# agouti.net
KiCad netlist of a schematic drawn in EAGLE
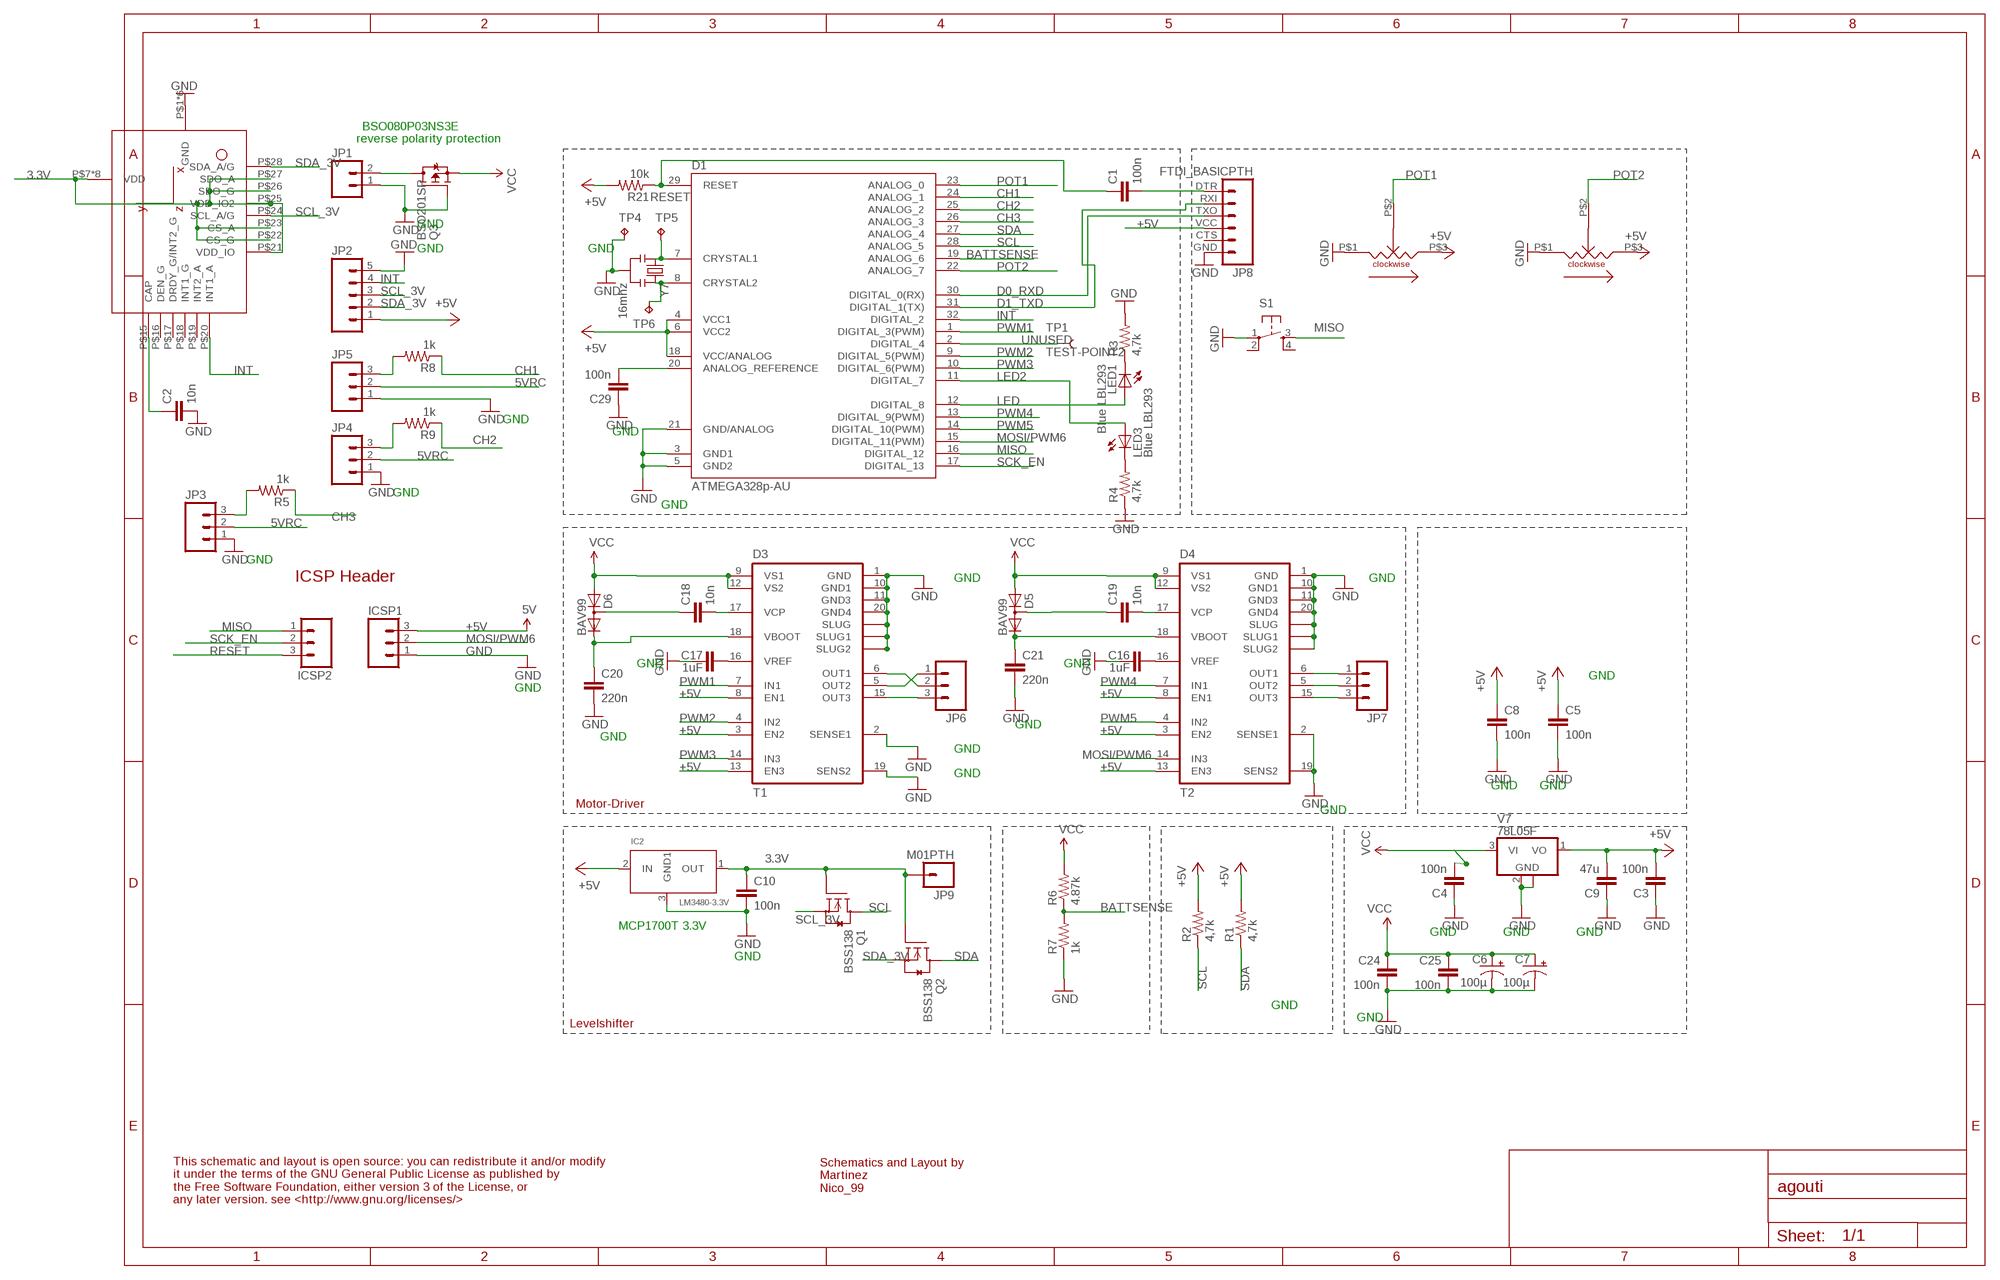
[diagram p0: schematic, sheet 1]

(export (version "E")
  (design (tool "Eeschema 10.0.6"))
  (components
    (comp (ref "C1")
      (value "100n")
      (footprint "eagle-import:0805")
      (libsource (lib "eagle-import") (part "CAP0805"))
    )
    (comp (ref "C2")
      (value "10n")
      (footprint "eagle-import:0805")
      (libsource (lib "eagle-import") (part "CAP0805"))
    )
    (comp (ref "C3")
      (value "100n")
      (footprint "eagle-import:0805")
      (libsource (lib "eagle-import") (part "CAP0805"))
    )
    (comp (ref "C4")
      (value "100n")
      (footprint "eagle-import:0805")
      (libsource (lib "eagle-import") (part "CAP0805"))
    )
    (comp (ref "C5")
      (value "100n")
      (footprint "eagle-import:0805")
      (libsource (lib "eagle-import") (part "CAP0805"))
    )
    (comp (ref "C6")
      (value "100µ")
      (footprint "eagle-import:PANASONIC_D")
      (libsource (lib "eagle-import") (part "CAP_POLD"))
    )
    (comp (ref "C7")
      (value "100µ")
      (footprint "eagle-import:PANASONIC_D")
      (libsource (lib "eagle-import") (part "CAP_POLD"))
    )
    (comp (ref "C8")
      (value "100n")
      (footprint "eagle-import:0805")
      (libsource (lib "eagle-import") (part "CAP0805"))
    )
    (comp (ref "C9")
      (value "47u")
      (footprint "eagle-import:C1210")
      (libsource (lib "eagle-import") (part "C-EUC1210"))
    )
    (comp (ref "C10")
      (value "100n")
      (footprint "eagle-import:0805")
      (libsource (lib "eagle-import") (part "CAP0805"))
    )
    (comp (ref "C16")
      (value "1uF")
      (footprint "eagle-import:0805")
      (libsource (lib "eagle-import") (part "CAP0805"))
    )
    (comp (ref "C17")
      (value "1uF")
      (footprint "eagle-import:0805")
      (libsource (lib "eagle-import") (part "CAP0805"))
    )
    (comp (ref "C18")
      (value "10n")
      (footprint "eagle-import:0805")
      (libsource (lib "eagle-import") (part "CAP0805"))
    )
    (comp (ref "C19")
      (value "10n")
      (footprint "eagle-import:0805")
      (libsource (lib "eagle-import") (part "CAP0805"))
    )
    (comp (ref "C20")
      (value "220n")
      (footprint "eagle-import:0805")
      (libsource (lib "eagle-import") (part "CAP0805"))
    )
    (comp (ref "C21")
      (value "220n")
      (footprint "eagle-import:0805")
      (libsource (lib "eagle-import") (part "CAP0805"))
    )
    (comp (ref "C24")
      (value "100n")
      (footprint "eagle-import:0805")
      (libsource (lib "eagle-import") (part "CAP0805"))
    )
    (comp (ref "C25")
      (value "100n")
      (footprint "eagle-import:0805")
      (libsource (lib "eagle-import") (part "CAP0805"))
    )
    (comp (ref "C29")
      (value "100n")
      (footprint "eagle-import:0805")
      (libsource (lib "eagle-import") (part "CAP0805"))
    )
    (comp (ref "D1")
      (value "ATMEGA328p-AU")
      (footprint "eagle-import:TQFP32-08")
      (libsource (lib "eagle-import") (part "ATMEGA168-AU"))
    )
    (comp (ref "D3")
      (value "T1")
      (footprint "eagle-import:SO20POWER2")
      (libsource (lib "eagle-import") (part "L6234"))
    )
    (comp (ref "D4")
      (value "T2")
      (footprint "eagle-import:SO20POWER2")
      (libsource (lib "eagle-import") (part "L6234"))
    )
    (comp (ref "D5")
      (value "BAV99")
      (footprint "eagle-import:SOT23")
      (libsource (lib "eagle-import") (part "BAV199"))
    )
    (comp (ref "D6")
      (value "BAV99")
      (footprint "eagle-import:SOT23")
      (libsource (lib "eagle-import") (part "BAV199"))
    )
    (comp (ref "IC2")
      (value "LM3480-3.3V")
      (footprint "eagle-import:SOT23")
      (libsource (lib "eagle-import") (part "VREG_MULTI2"))
    )
    (comp (ref "ICSP1")
      (value "M03PTH")
      (footprint "eagle-import:1X03")
      (libsource (lib "eagle-import") (part "SparkFun-Connectors_M03PTH"))
    )
    (comp (ref "ICSP2")
      (value "M03PTH")
      (footprint "eagle-import:1X03")
      (libsource (lib "eagle-import") (part "SparkFun-Connectors_M03PTH"))
    )
    (comp (ref "JP1")
      (value "M02PTH")
      (footprint "eagle-import:1X02")
      (libsource (lib "eagle-import") (part "M02PTH"))
    )
    (comp (ref "JP2")
      (value "M05PTH")
      (footprint "eagle-import:1X05")
      (libsource (lib "eagle-import") (part "M05PTH"))
    )
    (comp (ref "JP3")
      (value "M03PTH")
      (footprint "eagle-import:1X03")
      (libsource (lib "eagle-import") (part "SparkFun-Connectors_M03PTH"))
    )
    (comp (ref "JP4")
      (value "M03PTH")
      (footprint "eagle-import:1X03")
      (libsource (lib "eagle-import") (part "SparkFun-Connectors_M03PTH"))
    )
    (comp (ref "JP5")
      (value "M03PTH")
      (footprint "eagle-import:1X03")
      (libsource (lib "eagle-import") (part "SparkFun-Connectors_M03PTH"))
    )
    (comp (ref "JP6")
      (value "M03PTH")
      (footprint "eagle-import:1X03")
      (libsource (lib "eagle-import") (part "M03PTH"))
    )
    (comp (ref "JP7")
      (value "M03PTH")
      (footprint "eagle-import:1X03")
      (libsource (lib "eagle-import") (part "M03PTH"))
    )
    (comp (ref "JP8")
      (value "FTDI_BASICPTH")
      (footprint "eagle-import:FTDI_BASIC")
      (libsource (lib "eagle-import") (part "FTDI_BASICPTH"))
    )
    (comp (ref "JP9")
      (value "M01PTH")
      (footprint "eagle-import:1X01")
      (libsource (lib "eagle-import") (part "M01PTH"))
    )
    (comp (ref "LED1")
      (value "Blue LBL293")
      (footprint "eagle-import:CHIP-LED0603")
      (libsource (lib "eagle-import") (part "LEDCHIP-LED0603"))
    )
    (comp (ref "LED3")
      (value "Blue LBL293")
      (footprint "eagle-import:CHIP-LED0603")
      (libsource (lib "eagle-import") (part "LEDCHIP-LED0603"))
    )
    (comp (ref "Q1")
      (value "BSS138")
      (footprint "eagle-import:SOT23")
      (libsource (lib "eagle-import") (part "BSS138"))
    )
    (comp (ref "Q2")
      (value "BSS138")
      (footprint "eagle-import:SOT23")
      (libsource (lib "eagle-import") (part "BSS138"))
    )
    (comp (ref "Q3")
      (value "BSO201SP")
      (footprint "eagle-import:SO-8")
      (libsource (lib "eagle-import") (part "BSO201SP"))
    )
    (comp (ref "R1")
      (value "4,7k")
      (footprint "eagle-import:0805")
      (libsource (lib "eagle-import") (part "RESISTOR0805-RES"))
    )
    (comp (ref "R2")
      (value "4,7k")
      (footprint "eagle-import:0805")
      (libsource (lib "eagle-import") (part "RESISTOR0805-RES"))
    )
    (comp (ref "R3")
      (value "4,7k")
      (footprint "eagle-import:0805")
      (libsource (lib "eagle-import") (part "RESISTOR0805-RES"))
    )
    (comp (ref "R4")
      (value "4,7k")
      (footprint "eagle-import:0805")
      (libsource (lib "eagle-import") (part "RESISTOR0805-RES"))
    )
    (comp (ref "R5")
      (value "1k")
      (footprint "eagle-import:0805")
      (libsource (lib "eagle-import") (part "RESISTOR0805-RES"))
    )
    (comp (ref "R6")
      (value "4.87k")
      (footprint "eagle-import:0805")
      (libsource (lib "eagle-import") (part "RESISTOR0805-RES"))
    )
    (comp (ref "R7")
      (value "1k")
      (footprint "eagle-import:0805")
      (libsource (lib "eagle-import") (part "RESISTOR0805-RES"))
    )
    (comp (ref "R8")
      (value "1k")
      (footprint "eagle-import:0805")
      (libsource (lib "eagle-import") (part "RESISTOR0805-RES"))
    )
    (comp (ref "R9")
      (value "1k")
      (footprint "eagle-import:0805")
      (libsource (lib "eagle-import") (part "RESISTOR0805-RES"))
    )
    (comp (ref "R21")
      (value "10k")
      (footprint "eagle-import:0805")
      (libsource (lib "eagle-import") (part "RESISTOR0805-RES"))
    )
    (comp (ref "S1")
      (value "TAC_SWITCHSMD")
      (footprint "eagle-import:TACTILE_SWITCH_SMD")
      (libsource (lib "eagle-import") (part "TAC_SWITCHSMD"))
    )
    (comp (ref "TP1")
      (value "TEST-POINT2")
      (footprint "eagle-import:PAD.02X.02")
      (libsource (lib "eagle-import") (part "TEST-POINT2"))
    )
    (comp (ref "TP4")
      (value "TPTP06SQ")
      (footprint "eagle-import:TP06SQ")
      (libsource (lib "eagle-import") (part "TPTP06SQ"))
    )
    (comp (ref "TP5")
      (value "TPTP06SQ")
      (footprint "eagle-import:TP06SQ")
      (libsource (lib "eagle-import") (part "TPTP06SQ"))
    )
    (comp (ref "TP6")
      (value "TPTP06SQ")
      (footprint "eagle-import:TP06SQ")
      (libsource (lib "eagle-import") (part "TPTP06SQ"))
    )
    (comp (ref "U$3")
      (value "TRIMMERPOT")
      (footprint "eagle-import:BOURNES_3361P")
      (libsource (lib "eagle-import") (part "TRIMMERPOT"))
    )
    (comp (ref "U$5")
      (value "TRIMMERPOT")
      (footprint "eagle-import:BOURNES_3361P")
      (libsource (lib "eagle-import") (part "TRIMMERPOT"))
    )
    (comp (ref "U$6")
      (value "LSM330")
      (footprint "eagle-import:LGA-28")
      (libsource (lib "eagle-import") (part "LSM330"))
    )
    (comp (ref "V7")
      (value "78L05F")
      (footprint "eagle-import:SOT89")
      (libsource (lib "eagle-import") (part "78LF05"))
    )
    (comp (ref "Y7")
      (value "16mhz")
      (footprint "eagle-import:RESONATOR-SMD")
      (libsource (lib "eagle-import") (part "RESONATORSMD"))
    )
  )
  (nets
    (net (code "1") (name "+5V") (class "Default")
      (node (ref "C3") (pin "2") (pinfunction "2_2") (pintype "passive"))
      (node (ref "C5") (pin "1") (pinfunction "1_1") (pintype "passive"))
      (node (ref "C8") (pin "1") (pinfunction "1_1") (pintype "passive"))
      (node (ref "C9") (pin "2") (pinfunction "2_2") (pintype "passive"))
      (node (ref "D1") (pin "18") (pinfunction "VCC/ANALOG_18") (pintype "passive"))
      (node (ref "D1") (pin "4") (pinfunction "VCC1_4") (pintype "power_in"))
      (node (ref "D1") (pin "6") (pinfunction "VCC2_6") (pintype "power_in"))
      (node (ref "D3") (pin "13") (pinfunction "EN3_13") (pintype "output"))
      (node (ref "D3") (pin "3") (pinfunction "EN2_3") (pintype "input"))
      (node (ref "D3") (pin "8") (pinfunction "EN1_8") (pintype "bidirectional"))
      (node (ref "D4") (pin "13") (pinfunction "EN3_13") (pintype "output"))
      (node (ref "D4") (pin "3") (pinfunction "EN2_3") (pintype "input"))
      (node (ref "D4") (pin "8") (pinfunction "EN1_8") (pintype "bidirectional"))
      (node (ref "IC2") (pin "2") (pinfunction "IN_2") (pintype "power_in"))
      (node (ref "ICSP1") (pin "3") (pinfunction "3_3") (pintype "passive"))
      (node (ref "JP2") (pin "1") (pinfunction "1_1") (pintype "passive"))
      (node (ref "JP8") (pin "VCC") (pinfunction "4_VCC") (pintype "passive"))
      (node (ref "R1") (pin "2") (pinfunction "2_2") (pintype "passive"))
      (node (ref "R2") (pin "2") (pinfunction "2_2") (pintype "passive"))
      (node (ref "R21") (pin "2") (pinfunction "2_2") (pintype "passive"))
      (node (ref "U$3") (pin "P$3") (pinfunction "P$3_P$3") (pintype "bidirectional"))
      (node (ref "U$5") (pin "P$3") (pinfunction "P$3_P$3") (pintype "bidirectional"))
      (node (ref "V7") (pin "1") (pinfunction "VO_1") (pintype "passive"))
    )
    (net (code "2") (name "/3.3V") (class "Default")
      (node (ref "C10") (pin "1") (pinfunction "1_1") (pintype "passive"))
      (node (ref "IC2") (pin "1") (pinfunction "OUT_1") (pintype "power_in"))
      (node (ref "JP9") (pin "1") (pinfunction "1_1") (pintype "passive"))
      (node (ref "Q1") (pin "1") (pinfunction "G_1") (pintype "passive"))
      (node (ref "Q2") (pin "1") (pinfunction "G_1") (pintype "passive"))
      (node (ref "U$6") (pin "P$10") (pinfunction "VDD_P$10") (pintype "bidirectional"))
      (node (ref "U$6") (pin "P$11") (pinfunction "VDD_P$11") (pintype "bidirectional"))
      (node (ref "U$6") (pin "P$12") (pinfunction "VDD_P$12") (pintype "bidirectional"))
      (node (ref "U$6") (pin "P$13") (pinfunction "VDD_P$13") (pintype "bidirectional"))
      (node (ref "U$6") (pin "P$14") (pinfunction "VDD_P$14") (pintype "bidirectional"))
      (node (ref "U$6") (pin "P$21") (pinfunction "VDD_IO_P$21") (pintype "bidirectional"))
      (node (ref "U$6") (pin "P$22") (pinfunction "CS_G_P$22") (pintype "bidirectional"))
      (node (ref "U$6") (pin "P$23") (pinfunction "CS_A_P$23") (pintype "bidirectional"))
      (node (ref "U$6") (pin "P$25") (pinfunction "VDD_IO2_P$25") (pintype "bidirectional"))
      (node (ref "U$6") (pin "P$26") (pinfunction "SDO_G_P$26") (pintype "bidirectional"))
      (node (ref "U$6") (pin "P$27") (pinfunction "SDO_A_P$27") (pintype "bidirectional"))
      (node (ref "U$6") (pin "P$7") (pinfunction "VDD_P$7") (pintype "bidirectional"))
      (node (ref "U$6") (pin "P$8") (pinfunction "VDD_P$8") (pintype "bidirectional"))
      (node (ref "U$6") (pin "P$9") (pinfunction "VDD_P$9") (pintype "bidirectional"))
    )
    (net (code "3") (name "/5VRC") (class "Default")
      (node (ref "JP3") (pin "2") (pinfunction "2_2") (pintype "passive"))
      (node (ref "JP4") (pin "2") (pinfunction "2_2") (pintype "passive"))
      (node (ref "JP5") (pin "2") (pinfunction "2_2") (pintype "passive"))
    )
    (net (code "4") (name "/BATTSENSE") (class "Default")
      (node (ref "D1") (pin "19") (pinfunction "ANALOG_6_19") (pintype "passive"))
      (node (ref "R6") (pin "1") (pinfunction "1_1") (pintype "passive"))
      (node (ref "R7") (pin "2") (pinfunction "2_2") (pintype "passive"))
    )
    (net (code "5") (name "/CH1") (class "Default")
      (node (ref "D1") (pin "24") (pinfunction "ANALOG_1_24") (pintype "bidirectional"))
      (node (ref "R8") (pin "1") (pinfunction "1_1") (pintype "passive"))
    )
    (net (code "6") (name "/CH2") (class "Default")
      (node (ref "D1") (pin "25") (pinfunction "ANALOG_2_25") (pintype "bidirectional"))
      (node (ref "R9") (pin "1") (pinfunction "1_1") (pintype "passive"))
    )
    (net (code "7") (name "/CH3") (class "Default")
      (node (ref "D1") (pin "26") (pinfunction "ANALOG_3_26") (pintype "bidirectional"))
      (node (ref "R5") (pin "1") (pinfunction "1_1") (pintype "passive"))
    )
    (net (code "8") (name "/D0_RXD") (class "Default")
      (node (ref "D1") (pin "30") (pinfunction "DIGITAL_0(RX)_30") (pintype "bidirectional"))
      (node (ref "JP8") (pin "TXO") (pinfunction "3_TXO") (pintype "passive"))
    )
    (net (code "9") (name "/D1_TXD") (class "Default")
      (node (ref "D1") (pin "31") (pinfunction "DIGITAL_1(TX)_31") (pintype "bidirectional"))
      (node (ref "JP8") (pin "RXI") (pinfunction "2_RXI") (pintype "passive"))
    )
    (net (code "10") (name "/INT") (class "Default")
      (node (ref "D1") (pin "32") (pinfunction "DIGITAL_2_32") (pintype "bidirectional"))
      (node (ref "JP2") (pin "4") (pinfunction "4_4") (pintype "passive"))
      (node (ref "U$6") (pin "P$20") (pinfunction "INT1_A_P$20") (pintype "bidirectional"))
    )
    (net (code "11") (name "/LED") (class "Default")
      (node (ref "D1") (pin "12") (pinfunction "DIGITAL_8_12") (pintype "bidirectional"))
      (node (ref "LED1") (pin "A") (pinfunction "A_A") (pintype "passive"))
    )
    (net (code "12") (name "/LED2") (class "Default")
      (node (ref "D1") (pin "11") (pinfunction "DIGITAL_7_11") (pintype "bidirectional"))
      (node (ref "LED3") (pin "A") (pinfunction "A_A") (pintype "passive"))
    )
    (net (code "13") (name "/MISO") (class "Default")
      (node (ref "D1") (pin "16") (pinfunction "DIGITAL_12_16") (pintype "bidirectional"))
      (node (ref "ICSP2") (pin "1") (pinfunction "1_1") (pintype "passive"))
      (node (ref "S1") (pin "3") (pinfunction "3_3") (pintype "passive"))
    )
    (net (code "14") (name "/MOSI{slash}PWM6") (class "Default")
      (node (ref "D1") (pin "15") (pinfunction "DIGITAL_11(PWM)_15") (pintype "bidirectional"))
      (node (ref "D4") (pin "14") (pinfunction "IN3_14") (pintype "bidirectional"))
      (node (ref "ICSP1") (pin "2") (pinfunction "2_2") (pintype "passive"))
    )
    (net (code "15") (name "/POT1") (class "Default")
      (node (ref "D1") (pin "23") (pinfunction "ANALOG_0_23") (pintype "bidirectional"))
      (node (ref "U$3") (pin "P$2") (pinfunction "P$2_P$2") (pintype "bidirectional"))
    )
    (net (code "16") (name "/POT2") (class "Default")
      (node (ref "D1") (pin "22") (pinfunction "ANALOG_7_22") (pintype "passive"))
      (node (ref "U$5") (pin "P$2") (pinfunction "P$2_P$2") (pintype "bidirectional"))
    )
    (net (code "17") (name "/PWM1") (class "Default")
      (node (ref "D1") (pin "1") (pinfunction "DIGITAL_3(PWM)_1") (pintype "bidirectional"))
      (node (ref "D3") (pin "7") (pinfunction "IN1_7") (pintype "input"))
    )
    (net (code "18") (name "/PWM2") (class "Default")
      (node (ref "D1") (pin "9") (pinfunction "DIGITAL_5(PWM)_9") (pintype "bidirectional"))
      (node (ref "D3") (pin "4") (pinfunction "IN2_4") (pintype "input"))
    )
    (net (code "19") (name "/PWM3") (class "Default")
      (node (ref "D1") (pin "10") (pinfunction "DIGITAL_6(PWM)_10") (pintype "bidirectional"))
      (node (ref "D3") (pin "14") (pinfunction "IN3_14") (pintype "bidirectional"))
    )
    (net (code "20") (name "/PWM4") (class "Default")
      (node (ref "D1") (pin "13") (pinfunction "DIGITAL_9(PWM)_13") (pintype "bidirectional"))
      (node (ref "D4") (pin "7") (pinfunction "IN1_7") (pintype "input"))
    )
    (net (code "21") (name "/PWM5") (class "Default")
      (node (ref "D1") (pin "14") (pinfunction "DIGITAL_10(PWM)_14") (pintype "bidirectional"))
      (node (ref "D4") (pin "4") (pinfunction "IN2_4") (pintype "input"))
    )
    (net (code "22") (name "/RESET") (class "Default")
      (node (ref "C1") (pin "1") (pinfunction "1_1") (pintype "passive"))
      (node (ref "D1") (pin "29") (pinfunction "RESET_29") (pintype "bidirectional"))
      (node (ref "ICSP2") (pin "3") (pinfunction "3_3") (pintype "passive"))
      (node (ref "R21") (pin "1") (pinfunction "1_1") (pintype "passive"))
    )
    (net (code "23") (name "/SCK_EN") (class "Default")
      (node (ref "D1") (pin "17") (pinfunction "DIGITAL_13_17") (pintype "bidirectional"))
      (node (ref "ICSP2") (pin "2") (pinfunction "2_2") (pintype "passive"))
    )
    (net (code "24") (name "/SCL") (class "Default")
      (node (ref "D1") (pin "28") (pinfunction "ANALOG_5_28") (pintype "bidirectional"))
      (node (ref "Q1") (pin "3") (pinfunction "D_3") (pintype "passive"))
      (node (ref "R2") (pin "1") (pinfunction "1_1") (pintype "passive"))
    )
    (net (code "25") (name "/SCL_3V") (class "Default")
      (node (ref "JP2") (pin "3") (pinfunction "3_3") (pintype "passive"))
      (node (ref "Q1") (pin "2") (pinfunction "S_2") (pintype "passive"))
      (node (ref "U$6") (pin "P$24") (pinfunction "SCL_A/G_P$24") (pintype "bidirectional"))
    )
    (net (code "26") (name "/SDA") (class "Default")
      (node (ref "D1") (pin "27") (pinfunction "ANALOG_4_27") (pintype "bidirectional"))
      (node (ref "Q2") (pin "3") (pinfunction "D_3") (pintype "passive"))
      (node (ref "R1") (pin "1") (pinfunction "1_1") (pintype "passive"))
    )
    (net (code "27") (name "/SDA_3V") (class "Default")
      (node (ref "JP2") (pin "2") (pinfunction "2_2") (pintype "passive"))
      (node (ref "Q2") (pin "2") (pinfunction "S_2") (pintype "passive"))
      (node (ref "U$6") (pin "P$28") (pinfunction "SDA_A/G_P$28") (pintype "bidirectional"))
    )
    (net (code "28") (name "/UNUSED") (class "Default")
      (node (ref "D1") (pin "2") (pinfunction "DIGITAL_4_2") (pintype "bidirectional"))
      (node (ref "TP1") (pin "P$1") (pinfunction "1_P$1") (pintype "bidirectional"))
    )
    (net (code "29") (name "GND") (class "Default")
      (node (ref "C10") (pin "2") (pinfunction "2_2") (pintype "passive"))
      (node (ref "C16") (pin "1") (pinfunction "1_1") (pintype "passive"))
      (node (ref "C17") (pin "1") (pinfunction "1_1") (pintype "passive"))
      (node (ref "C2") (pin "2") (pinfunction "2_2") (pintype "passive"))
      (node (ref "C20") (pin "2") (pinfunction "2_2") (pintype "passive"))
      (node (ref "C21") (pin "2") (pinfunction "2_2") (pintype "passive"))
      (node (ref "C24") (pin "2") (pinfunction "2_2") (pintype "passive"))
      (node (ref "C25") (pin "2") (pinfunction "2_2") (pintype "passive"))
      (node (ref "C29") (pin "1") (pinfunction "1_1") (pintype "passive"))
      (node (ref "C3") (pin "1") (pinfunction "1_1") (pintype "passive"))
      (node (ref "C4") (pin "1") (pinfunction "1_1") (pintype "passive"))
      (node (ref "C5") (pin "2") (pinfunction "2_2") (pintype "passive"))
      (node (ref "C6") (pin "-") (pinfunction "-_-") (pintype "passive"))
      (node (ref "C7") (pin "-") (pinfunction "-_-") (pintype "passive"))
      (node (ref "C8") (pin "2") (pinfunction "2_2") (pintype "passive"))
      (node (ref "C9") (pin "1") (pinfunction "1_1") (pintype "passive"))
      (node (ref "D1") (pin "21") (pinfunction "GND/ANALOG_21") (pintype "power_in"))
      (node (ref "D1") (pin "3") (pinfunction "GND1_3") (pintype "power_in"))
      (node (ref "D1") (pin "5") (pinfunction "GND2_5") (pintype "power_in"))
      (node (ref "D3") (pin "1") (pinfunction "GND_1") (pintype "power_in"))
      (node (ref "D3") (pin "10") (pinfunction "GND1_10") (pintype "power_in"))
      (node (ref "D3") (pin "11") (pinfunction "GND3_11") (pintype "power_in"))
      (node (ref "D3") (pin "19") (pinfunction "SENS2_19") (pintype "power_in"))
      (node (ref "D3") (pin "2") (pinfunction "SENSE1_2") (pintype "output"))
      (node (ref "D3") (pin "20") (pinfunction "GND4_20") (pintype "power_in"))
      (node (ref "D3") (pin "SLUG") (pinfunction "SLUG1_SLUG") (pintype "power_in"))
      (node (ref "D3") (pin "SLUG1") (pinfunction "SLUG2_SLUG1") (pintype "power_in"))
      (node (ref "D3") (pin "SLUG2") (pinfunction "SLUG_SLUG2") (pintype "power_in"))
      (node (ref "D4") (pin "1") (pinfunction "GND_1") (pintype "power_in"))
      (node (ref "D4") (pin "10") (pinfunction "GND1_10") (pintype "power_in"))
      (node (ref "D4") (pin "11") (pinfunction "GND3_11") (pintype "power_in"))
      (node (ref "D4") (pin "19") (pinfunction "SENS2_19") (pintype "power_in"))
      (node (ref "D4") (pin "2") (pinfunction "SENSE1_2") (pintype "output"))
      (node (ref "D4") (pin "20") (pinfunction "GND4_20") (pintype "power_in"))
      (node (ref "D4") (pin "SLUG") (pinfunction "SLUG1_SLUG") (pintype "power_in"))
      (node (ref "D4") (pin "SLUG1") (pinfunction "SLUG2_SLUG1") (pintype "power_in"))
      (node (ref "D4") (pin "SLUG2") (pinfunction "SLUG_SLUG2") (pintype "power_in"))
      (node (ref "IC2") (pin "3") (pinfunction "GND1_3") (pintype "power_in"))
      (node (ref "ICSP1") (pin "1") (pinfunction "1_1") (pintype "passive"))
      (node (ref "JP1") (pin "1") (pinfunction "1_1") (pintype "passive"))
      (node (ref "JP2") (pin "5") (pinfunction "5_5") (pintype "passive"))
      (node (ref "JP3") (pin "1") (pinfunction "1_1") (pintype "passive"))
      (node (ref "JP4") (pin "1") (pinfunction "1_1") (pintype "passive"))
      (node (ref "JP5") (pin "1") (pinfunction "1_1") (pintype "passive"))
      (node (ref "JP8") (pin "GND") (pinfunction "6_GND") (pintype "passive"))
      (node (ref "Q3") (pin "4") (pinfunction "G_4") (pintype "passive"))
      (node (ref "R3") (pin "2") (pinfunction "2_2") (pintype "passive"))
      (node (ref "R4") (pin "1") (pinfunction "1_1") (pintype "passive"))
      (node (ref "R7") (pin "1") (pinfunction "1_1") (pintype "passive"))
      (node (ref "S1") (pin "1") (pinfunction "1_1") (pintype "passive"))
      (node (ref "TP4") (pin "TP") (pinfunction "TP_TP") (pintype "input"))
      (node (ref "U$3") (pin "P$1") (pinfunction "P$1_P$1") (pintype "bidirectional"))
      (node (ref "U$5") (pin "P$1") (pinfunction "P$1_P$1") (pintype "bidirectional"))
      (node (ref "U$6") (pin "P$1") (pinfunction "GND_P$1") (pintype "bidirectional"))
      (node (ref "U$6") (pin "P$2") (pinfunction "GND_P$2") (pintype "bidirectional"))
      (node (ref "U$6") (pin "P$3") (pinfunction "GND_P$3") (pintype "bidirectional"))
      (node (ref "U$6") (pin "P$4") (pinfunction "GND_P$4") (pintype "bidirectional"))
      (node (ref "U$6") (pin "P$5") (pinfunction "GND_P$5") (pintype "bidirectional"))
      (node (ref "U$6") (pin "P$6") (pinfunction "GND_P$6") (pintype "bidirectional"))
      (node (ref "V7") (pin "2") (pinfunction "GND_2") (pintype "passive"))
      (node (ref "V7") (pin "2@1") (pinfunction "GND_2@1") (pintype "passive"))
      (node (ref "Y7") (pin "2") (pinfunction "2_2") (pintype "passive"))
    )
    (net (code "30") (name "Net-(D1-ANALOG_REFERENCE)") (class "Default")
      (node (ref "C29") (pin "2") (pinfunction "2_2") (pintype "passive"))
      (node (ref "D1") (pin "20") (pinfunction "ANALOG_REFERENCE_20") (pintype "passive"))
    )
    (net (code "31") (name "Net-(D1-CRYSTAL1)") (class "Default")
      (node (ref "D1") (pin "7") (pinfunction "CRYSTAL1_7") (pintype "bidirectional"))
      (node (ref "TP5") (pin "TP") (pinfunction "TP_TP") (pintype "input"))
      (node (ref "Y7") (pin "1") (pinfunction "1_1") (pintype "passive"))
    )
    (net (code "32") (name "Net-(D1-CRYSTAL2)") (class "Default")
      (node (ref "D1") (pin "8") (pinfunction "CRYSTAL2_8") (pintype "bidirectional"))
      (node (ref "TP6") (pin "TP") (pinfunction "TP_TP") (pintype "input"))
      (node (ref "Y7") (pin "3") (pinfunction "3_3") (pintype "passive"))
    )
    (net (code "33") (name "Net-(D3-OUT1)") (class "Default")
      (node (ref "D3") (pin "6") (pinfunction "OUT1_6") (pintype "output"))
      (node (ref "JP6") (pin "2") (pinfunction "2_2") (pintype "passive"))
    )
    (net (code "34") (name "Net-(D3-OUT2)") (class "Default")
      (node (ref "D3") (pin "5") (pinfunction "OUT2_5") (pintype "output"))
      (node (ref "JP6") (pin "1") (pinfunction "1_1") (pintype "passive"))
    )
    (net (code "35") (name "Net-(D3-OUT3)") (class "Default")
      (node (ref "D3") (pin "15") (pinfunction "OUT3_15") (pintype "power_in"))
      (node (ref "JP6") (pin "3") (pinfunction "3_3") (pintype "passive"))
    )
    (net (code "36") (name "Net-(D3-VBOOT)") (class "Default")
      (node (ref "C20") (pin "1") (pinfunction "1_1") (pintype "passive"))
      (node (ref "D3") (pin "18") (pinfunction "VBOOT_18") (pintype "passive"))
      (node (ref "D6") (pin "2") (pinfunction "C_2") (pintype "passive"))
    )
    (net (code "37") (name "Net-(D3-VCP)") (class "Default")
      (node (ref "C18") (pin "2") (pinfunction "2_2") (pintype "passive"))
      (node (ref "D3") (pin "17") (pinfunction "VCP_17") (pintype "passive"))
    )
    (net (code "38") (name "Net-(D3-VREF)") (class "Default")
      (node (ref "C17") (pin "2") (pinfunction "2_2") (pintype "passive"))
      (node (ref "D3") (pin "16") (pinfunction "VREF_16") (pintype "input"))
    )
    (net (code "39") (name "Net-(D4-OUT1)") (class "Default")
      (node (ref "D4") (pin "6") (pinfunction "OUT1_6") (pintype "output"))
      (node (ref "JP7") (pin "1") (pinfunction "1_1") (pintype "passive"))
    )
    (net (code "40") (name "Net-(D4-OUT2)") (class "Default")
      (node (ref "D4") (pin "5") (pinfunction "OUT2_5") (pintype "output"))
      (node (ref "JP7") (pin "2") (pinfunction "2_2") (pintype "passive"))
    )
    (net (code "41") (name "Net-(D4-OUT3)") (class "Default")
      (node (ref "D4") (pin "15") (pinfunction "OUT3_15") (pintype "power_in"))
      (node (ref "JP7") (pin "3") (pinfunction "3_3") (pintype "passive"))
    )
    (net (code "42") (name "Net-(D4-VBOOT)") (class "Default")
      (node (ref "C21") (pin "1") (pinfunction "1_1") (pintype "passive"))
      (node (ref "D4") (pin "18") (pinfunction "VBOOT_18") (pintype "passive"))
      (node (ref "D5") (pin "2") (pinfunction "C_2") (pintype "passive"))
    )
    (net (code "43") (name "Net-(D4-VCP)") (class "Default")
      (node (ref "C19") (pin "2") (pinfunction "2_2") (pintype "passive"))
      (node (ref "D4") (pin "17") (pinfunction "VCP_17") (pintype "passive"))
    )
    (net (code "44") (name "Net-(D4-VREF)") (class "Default")
      (node (ref "C16") (pin "2") (pinfunction "2_2") (pintype "passive"))
      (node (ref "D4") (pin "16") (pinfunction "VREF_16") (pintype "input"))
    )
    (net (code "45") (name "Net-(D5-AC)") (class "Default")
      (node (ref "C19") (pin "1") (pinfunction "1_1") (pintype "passive"))
      (node (ref "D5") (pin "3") (pinfunction "AC_3") (pintype "passive"))
    )
    (net (code "46") (name "Net-(D6-AC)") (class "Default")
      (node (ref "C18") (pin "1") (pinfunction "1_1") (pintype "passive"))
      (node (ref "D6") (pin "3") (pinfunction "AC_3") (pintype "passive"))
    )
    (net (code "47") (name "Net-(JP1-Pad2)") (class "Default")
      (node (ref "JP1") (pin "2") (pinfunction "2_2") (pintype "passive"))
      (node (ref "Q3") (pin "5") (pinfunction "D_5") (pintype "passive"))
      (node (ref "Q3") (pin "6") (pinfunction "D_6") (pintype "passive"))
      (node (ref "Q3") (pin "7") (pinfunction "D_7") (pintype "passive"))
      (node (ref "Q3") (pin "8") (pinfunction "D_8") (pintype "passive"))
    )
    (net (code "48") (name "Net-(JP3-Pad3)") (class "Default")
      (node (ref "JP3") (pin "3") (pinfunction "3_3") (pintype "passive"))
      (node (ref "R5") (pin "2") (pinfunction "2_2") (pintype "passive"))
    )
    (net (code "49") (name "Net-(JP4-Pad3)") (class "Default")
      (node (ref "JP4") (pin "3") (pinfunction "3_3") (pintype "passive"))
      (node (ref "R9") (pin "2") (pinfunction "2_2") (pintype "passive"))
    )
    (net (code "50") (name "Net-(JP5-Pad3)") (class "Default")
      (node (ref "JP5") (pin "3") (pinfunction "3_3") (pintype "passive"))
      (node (ref "R8") (pin "2") (pinfunction "2_2") (pintype "passive"))
    )
    (net (code "51") (name "Net-(JP8-1)") (class "Default")
      (node (ref "C1") (pin "2") (pinfunction "2_2") (pintype "passive"))
      (node (ref "JP8") (pin "DTR") (pinfunction "1_DTR") (pintype "passive"))
    )
    (net (code "52") (name "Net-(LED1-PadC)") (class "Default")
      (node (ref "LED1") (pin "C") (pinfunction "C_C") (pintype "passive"))
      (node (ref "R3") (pin "1") (pinfunction "1_1") (pintype "passive"))
    )
    (net (code "53") (name "Net-(LED3-PadC)") (class "Default")
      (node (ref "LED3") (pin "C") (pinfunction "C_C") (pintype "passive"))
      (node (ref "R4") (pin "2") (pinfunction "2_2") (pintype "passive"))
    )
    (net (code "54") (name "Net-(U$6-CAP)") (class "Default")
      (node (ref "C2") (pin "1") (pinfunction "1_1") (pintype "passive"))
      (node (ref "U$6") (pin "P$15") (pinfunction "CAP_P$15") (pintype "bidirectional"))
    )
    (net (code "55") (name "VCC") (class "Default")
      (node (ref "C24") (pin "1") (pinfunction "1_1") (pintype "passive"))
      (node (ref "C25") (pin "1") (pinfunction "1_1") (pintype "passive"))
      (node (ref "C4") (pin "2") (pinfunction "2_2") (pintype "passive"))
      (node (ref "C6") (pin "+") (pinfunction "+_+") (pintype "passive"))
      (node (ref "C7") (pin "+") (pinfunction "+_+") (pintype "passive"))
      (node (ref "D3") (pin "12") (pinfunction "VS2_12") (pintype "power_in"))
      (node (ref "D3") (pin "9") (pinfunction "VS1_9") (pintype "power_in"))
      (node (ref "D4") (pin "12") (pinfunction "VS2_12") (pintype "power_in"))
      (node (ref "D4") (pin "9") (pinfunction "VS1_9") (pintype "power_in"))
      (node (ref "D5") (pin "1") (pinfunction "A_1") (pintype "passive"))
      (node (ref "D6") (pin "1") (pinfunction "A_1") (pintype "passive"))
      (node (ref "Q3") (pin "1") (pinfunction "S_1") (pintype "passive"))
      (node (ref "Q3") (pin "2") (pinfunction "S_2") (pintype "passive"))
      (node (ref "Q3") (pin "3") (pinfunction "S_3") (pintype "passive"))
      (node (ref "R6") (pin "2") (pinfunction "2_2") (pintype "passive"))
      (node (ref "V7") (pin "3") (pinfunction "VI_3") (pintype "input"))
    )
    (net (code "56") (name "unconnected-(JP8-5-PadCTS)") (class "Default")
      (node (ref "JP8") (pin "CTS") (pinfunction "5_CTS") (pintype "passive"))
    )
    (net (code "57") (name "unconnected-(S1-Pad2)") (class "Default")
      (node (ref "S1") (pin "2") (pinfunction "2_2") (pintype "passive"))
    )
    (net (code "58") (name "unconnected-(S1-Pad4)") (class "Default")
      (node (ref "S1") (pin "4") (pinfunction "4_4") (pintype "passive"))
    )
    (net (code "59") (name "unconnected-(U$6-DEN_G-PadP$16)") (class "Default")
      (node (ref "U$6") (pin "P$16") (pinfunction "DEN_G_P$16") (pintype "bidirectional"))
    )
    (net (code "60") (name "unconnected-(U$6-DRDY_G{slash}INT2_G-PadP$17)") (class "Default")
      (node (ref "U$6") (pin "P$17") (pinfunction "DRDY_G/INT2_G_P$17") (pintype "bidirectional"))
    )
    (net (code "61") (name "unconnected-(U$6-INT1_G-PadP$18)") (class "Default")
      (node (ref "U$6") (pin "P$18") (pinfunction "INT1_G_P$18") (pintype "bidirectional"))
    )
    (net (code "62") (name "unconnected-(U$6-INT2_A-PadP$19)") (class "Default")
      (node (ref "U$6") (pin "P$19") (pinfunction "INT2_A_P$19") (pintype "bidirectional"))
    )
  )
)
